# 130812_AriloTX_FINAL.net
KiCad netlist of a schematic drawn in EAGLE
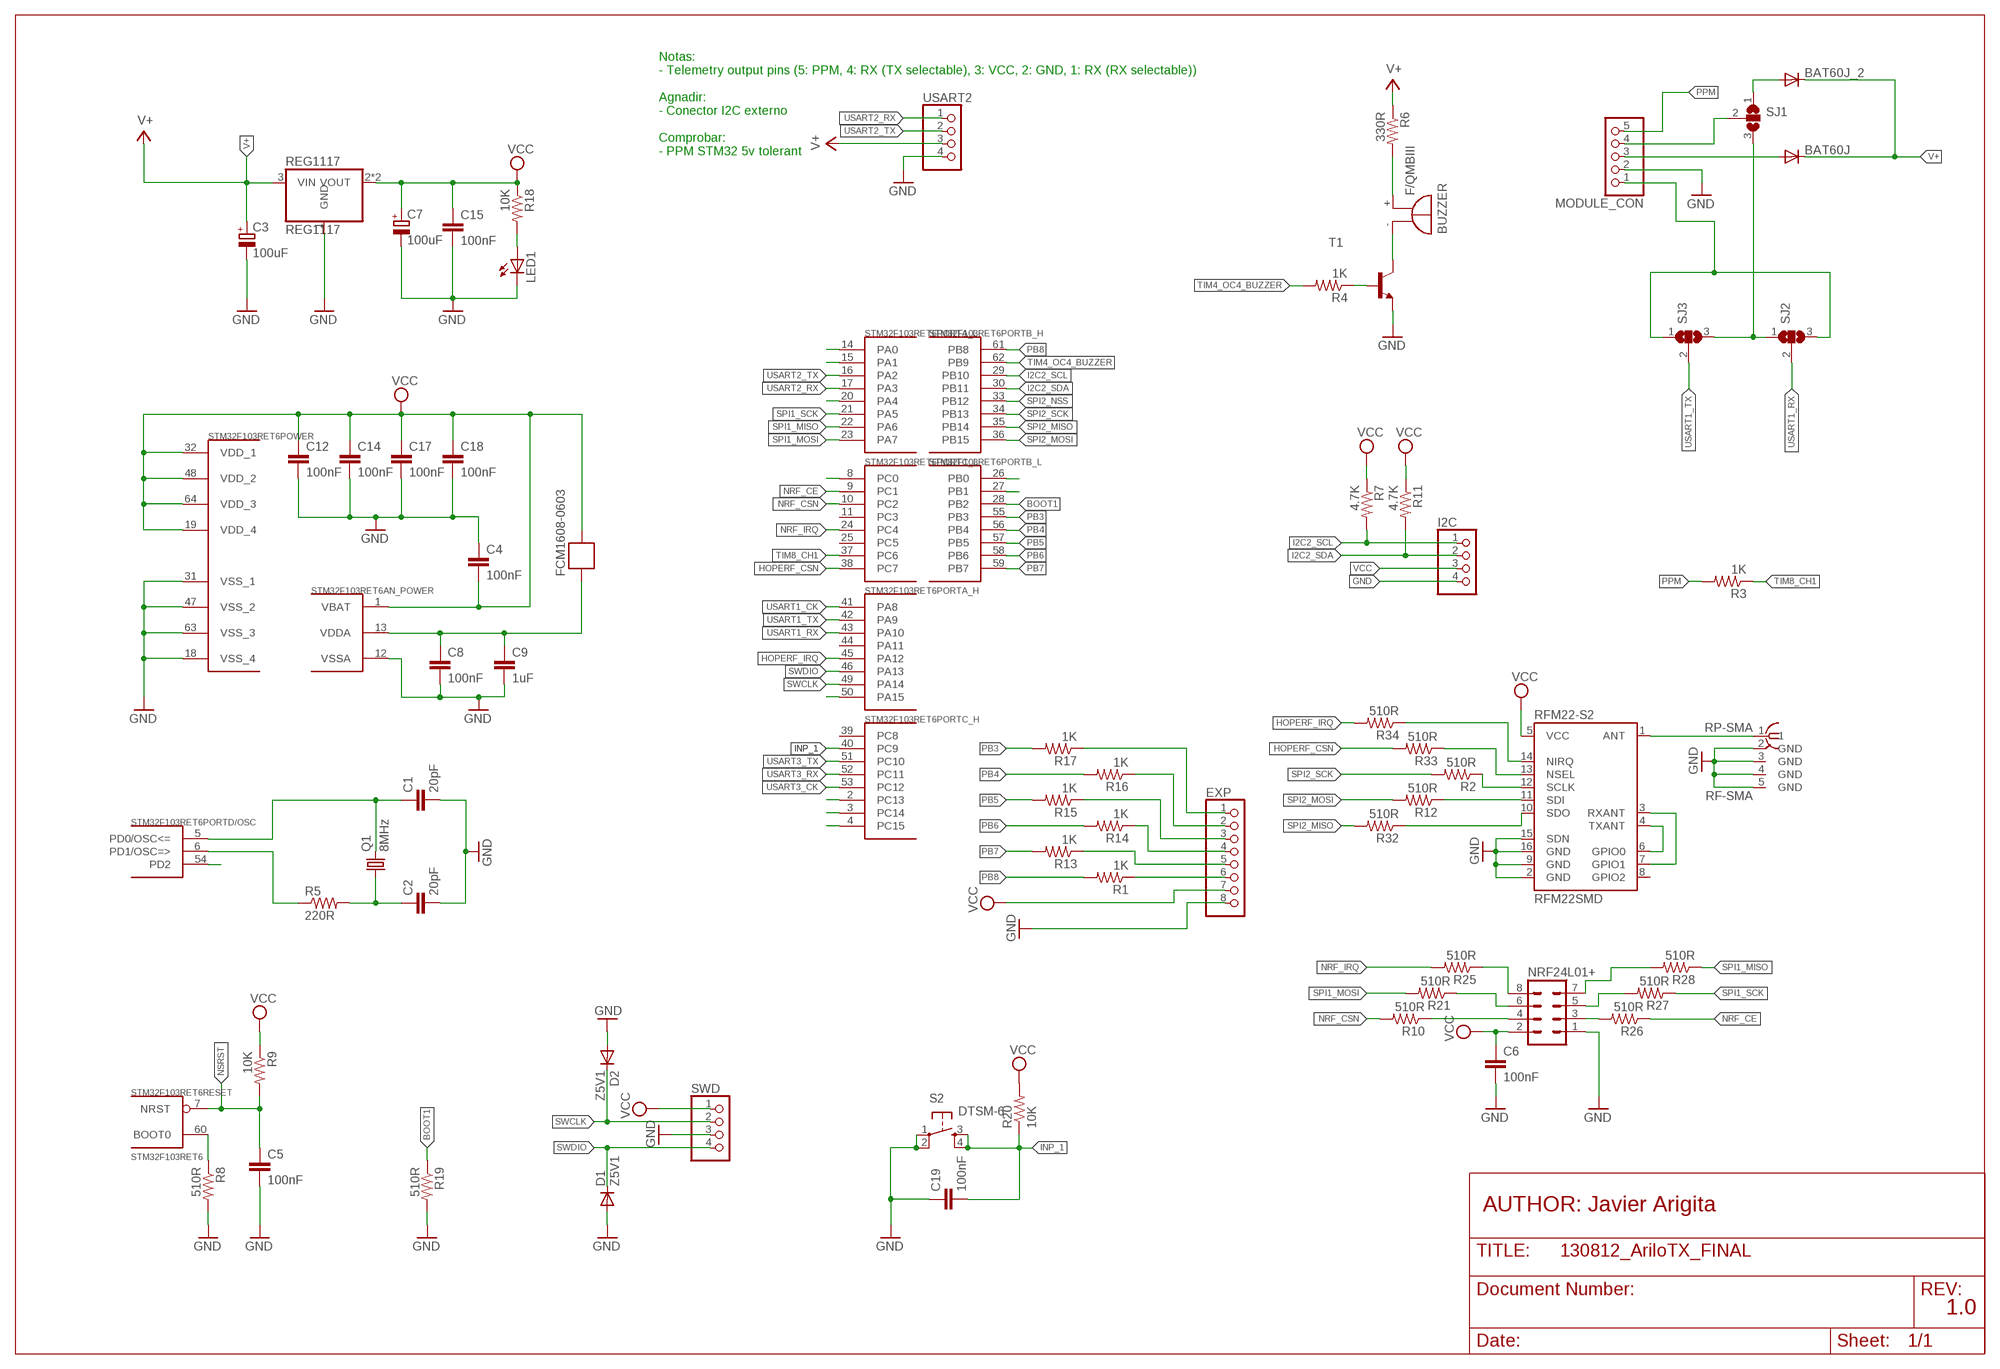
[diagram p0: schematic, sheet 1]

(export (version "E")
  (design (tool "Eeschema 10.0.6"))
  (components
    (comp (ref "BAT60J")
      (value "DIODE-SOD323-R")
      (footprint "eagle-import:SOD323-R")
      (libsource (lib "eagle-import") (part "DIODE-SOD323-R"))
    )
    (comp (ref "BAT60J_2")
      (value "DIODE-SOD323-R")
      (footprint "eagle-import:SOD323-R")
      (libsource (lib "eagle-import") (part "DIODE-SOD323-R"))
    )
    (comp (ref "BUZZER")
      (value "F/QMBIII")
      (footprint "eagle-import:F_QMBIII")
      (libsource (lib "eagle-import") (part "F/QMBIII"))
    )
    (comp (ref "C1")
      (value "20pF")
      (footprint "eagle-import:C0805")
      (libsource (lib "eagle-import") (part "C-EUC0805"))
    )
    (comp (ref "C2")
      (value "20pF")
      (footprint "eagle-import:C0805")
      (libsource (lib "eagle-import") (part "C-EUC0805"))
    )
    (comp (ref "C3")
      (value "100uF")
      (footprint "eagle-import:SMC_B")
      (libsource (lib "eagle-import") (part "CPOL-EUSMCB"))
    )
    (comp (ref "C4")
      (value "100nF")
      (footprint "eagle-import:C0805")
      (libsource (lib "eagle-import") (part "C-EUC0805"))
    )
    (comp (ref "C5")
      (value "100nF")
      (footprint "eagle-import:C0805")
      (libsource (lib "eagle-import") (part "C-EUC0805"))
    )
    (comp (ref "C6")
      (value "100nF")
      (footprint "eagle-import:C0805")
      (libsource (lib "eagle-import") (part "C-EUC0805"))
    )
    (comp (ref "C7")
      (value "100uF")
      (footprint "eagle-import:SMC_B")
      (libsource (lib "eagle-import") (part "CPOL-EUSMCB"))
    )
    (comp (ref "C8")
      (value "100nF")
      (footprint "eagle-import:C0805")
      (libsource (lib "eagle-import") (part "C-EUC0805"))
    )
    (comp (ref "C9")
      (value "1uF")
      (footprint "eagle-import:C3216")
      (libsource (lib "eagle-import") (part "resistor_C-EUC3216"))
    )
    (comp (ref "C12")
      (value "100nF")
      (footprint "eagle-import:C0805")
      (libsource (lib "eagle-import") (part "C-EUC0805"))
    )
    (comp (ref "C14")
      (value "100nF")
      (footprint "eagle-import:C0805")
      (libsource (lib "eagle-import") (part "C-EUC0805"))
    )
    (comp (ref "C15")
      (value "100nF")
      (footprint "eagle-import:C0805")
      (libsource (lib "eagle-import") (part "C-EUC0805"))
    )
    (comp (ref "C17")
      (value "100nF")
      (footprint "eagle-import:C0805")
      (libsource (lib "eagle-import") (part "C-EUC0805"))
    )
    (comp (ref "C18")
      (value "100nF")
      (footprint "eagle-import:C0805")
      (libsource (lib "eagle-import") (part "C-EUC0805"))
    )
    (comp (ref "C19")
      (value "100nF")
      (footprint "eagle-import:C0805")
      (libsource (lib "eagle-import") (part "C-EUC0805"))
    )
    (comp (ref "D1")
      (value "Z5V1")
      (footprint "eagle-import:SOD323-R")
      (libsource (lib "eagle-import") (part "DIODE-SOD323-R"))
    )
    (comp (ref "D2")
      (value "Z5V1")
      (footprint "eagle-import:SOD323-R")
      (libsource (lib "eagle-import") (part "DIODE-SOD323-R"))
    )
    (comp (ref "EXP")
      (value "PINHD-1X8")
      (footprint "eagle-import:1X08")
      (libsource (lib "eagle-import") (part "PINHD-1X8"))
    )
    (comp (ref "FCM1608-0603")
      (value "FERRITE-BEAD")
      (footprint "eagle-import:R0603")
      (libsource (lib "eagle-import") (part "FERRITE-BEAD"))
    )
    (comp (ref "I2C")
      (value "PINHD-1X4")
      (footprint "eagle-import:1X04")
      (libsource (lib "eagle-import") (part "PINHD-1X4"))
    )
    (comp (ref "LED1")
      (value "LED0805")
      (footprint "eagle-import:CHIPLED_0805")
      (libsource (lib "eagle-import") (part "LED0805"))
    )
    (comp (ref "MODULE_CON")
      (value "PINHD-1X5")
      (footprint "eagle-import:1X05")
      (libsource (lib "eagle-import") (part "PINHD-1X5"))
    )
    (comp (ref "NRF24L01+")
      (value "MA04-2")
      (footprint "eagle-import:MA04-2")
      (libsource (lib "eagle-import") (part "MA04-2"))
    )
    (comp (ref "Q1")
      (value "8MHz")
      (footprint "eagle-import:SM49")
      (libsource (lib "eagle-import") (part "CRYSTALSM49"))
    )
    (comp (ref "R1")
      (value "1K")
      (footprint "eagle-import:R0805")
      (libsource (lib "eagle-import") (part "RESISTOR0805"))
    )
    (comp (ref "R2")
      (value "510R")
      (footprint "eagle-import:R0805")
      (libsource (lib "eagle-import") (part "RESISTOR0805"))
    )
    (comp (ref "R3")
      (value "1K")
      (footprint "eagle-import:R0805")
      (libsource (lib "eagle-import") (part "RESISTOR0805"))
    )
    (comp (ref "R4")
      (value "1K")
      (footprint "eagle-import:R0805")
      (libsource (lib "eagle-import") (part "RESISTOR0805"))
    )
    (comp (ref "R5")
      (value "220R")
      (footprint "eagle-import:R0805")
      (libsource (lib "eagle-import") (part "RESISTOR0805"))
    )
    (comp (ref "R6")
      (value "330R")
      (footprint "eagle-import:R0805")
      (libsource (lib "eagle-import") (part "RESISTOR0805"))
    )
    (comp (ref "R7")
      (value "4.7K")
      (footprint "eagle-import:R0805")
      (libsource (lib "eagle-import") (part "RESISTOR0805"))
    )
    (comp (ref "R8")
      (value "510R")
      (footprint "eagle-import:R0805")
      (libsource (lib "eagle-import") (part "RESISTOR0805"))
    )
    (comp (ref "R9")
      (value "10K")
      (footprint "eagle-import:R0805")
      (libsource (lib "eagle-import") (part "RESISTOR0805"))
    )
    (comp (ref "R10")
      (value "510R")
      (footprint "eagle-import:R0805")
      (libsource (lib "eagle-import") (part "RESISTOR0805"))
    )
    (comp (ref "R11")
      (value "4.7K")
      (footprint "eagle-import:R0805")
      (libsource (lib "eagle-import") (part "RESISTOR0805"))
    )
    (comp (ref "R12")
      (value "510R")
      (footprint "eagle-import:R0805")
      (libsource (lib "eagle-import") (part "RESISTOR0805"))
    )
    (comp (ref "R13")
      (value "1K")
      (footprint "eagle-import:R0805")
      (libsource (lib "eagle-import") (part "RESISTOR0805"))
    )
    (comp (ref "R14")
      (value "1K")
      (footprint "eagle-import:R0805")
      (libsource (lib "eagle-import") (part "RESISTOR0805"))
    )
    (comp (ref "R15")
      (value "1K")
      (footprint "eagle-import:R0805")
      (libsource (lib "eagle-import") (part "RESISTOR0805"))
    )
    (comp (ref "R16")
      (value "1K")
      (footprint "eagle-import:R0805")
      (libsource (lib "eagle-import") (part "RESISTOR0805"))
    )
    (comp (ref "R17")
      (value "1K")
      (footprint "eagle-import:R0805")
      (libsource (lib "eagle-import") (part "RESISTOR0805"))
    )
    (comp (ref "R18")
      (value "10K")
      (footprint "eagle-import:R0805")
      (libsource (lib "eagle-import") (part "RESISTOR0805"))
    )
    (comp (ref "R19")
      (value "510R")
      (footprint "eagle-import:R0805")
      (libsource (lib "eagle-import") (part "RESISTOR0805"))
    )
    (comp (ref "R20")
      (value "10K")
      (footprint "eagle-import:R0805")
      (libsource (lib "eagle-import") (part "RESISTOR0805"))
    )
    (comp (ref "R21")
      (value "510R")
      (footprint "eagle-import:R0805")
      (libsource (lib "eagle-import") (part "RESISTOR0805"))
    )
    (comp (ref "R25")
      (value "510R")
      (footprint "eagle-import:R0805")
      (libsource (lib "eagle-import") (part "RESISTOR0805"))
    )
    (comp (ref "R26")
      (value "510R")
      (footprint "eagle-import:R0805")
      (libsource (lib "eagle-import") (part "RESISTOR0805"))
    )
    (comp (ref "R27")
      (value "510R")
      (footprint "eagle-import:R0805")
      (libsource (lib "eagle-import") (part "RESISTOR0805"))
    )
    (comp (ref "R28")
      (value "510R")
      (footprint "eagle-import:R0805")
      (libsource (lib "eagle-import") (part "RESISTOR0805"))
    )
    (comp (ref "R32")
      (value "510R")
      (footprint "eagle-import:R0805")
      (libsource (lib "eagle-import") (part "RESISTOR0805"))
    )
    (comp (ref "R33")
      (value "510R")
      (footprint "eagle-import:R0805")
      (libsource (lib "eagle-import") (part "RESISTOR0805"))
    )
    (comp (ref "R34")
      (value "510R")
      (footprint "eagle-import:R0805")
      (libsource (lib "eagle-import") (part "RESISTOR0805"))
    )
    (comp (ref "REG1117")
      (value "REG1117")
      (footprint "eagle-import:SOT223")
      (libsource (lib "eagle-import") (part "REG1117"))
    )
    (comp (ref "RFM22-S2")
      (value "RFM22SMD")
      (footprint "eagle-import:RFM22-XXX-S2")
      (libsource (lib "eagle-import") (part "RFM22SMD"))
    )
    (comp (ref "RP-SMA")
      (value "RF-SMA")
      (footprint "eagle-import:BU-SMA-H")
      (libsource (lib "eagle-import") (part "RF-SMA"))
    )
    (comp (ref "S2")
      (value "DTSM-6")
      (footprint "eagle-import:DTSM-6")
      (libsource (lib "eagle-import") (part "DTSM-6"))
    )
    (comp (ref "SJ1")
      (value "SJ2W")
      (footprint "eagle-import:SJ_2")
      (libsource (lib "eagle-import") (part "SJ2W"))
    )
    (comp (ref "SJ2")
      (value "SJ2W")
      (footprint "eagle-import:SJ_2")
      (libsource (lib "eagle-import") (part "SJ2W"))
    )
    (comp (ref "SJ3")
      (value "SJ2W")
      (footprint "eagle-import:SJ_2")
      (libsource (lib "eagle-import") (part "SJ2W"))
    )
    (comp (ref "STM32F103RET6")
      (value "STM32F103RET6")
      (footprint "eagle-import:TQFP64")
      (libsource (lib "eagle-import") (part "STM32F10XRXT6"))
    )
    (comp (ref "SWD")
      (value "PINHD-1X4")
      (footprint "eagle-import:1X04")
      (libsource (lib "eagle-import") (part "PINHD-1X4"))
    )
    (comp (ref "T1")
      (value "BC848-NPN-SOT23-BEC")
      (footprint "eagle-import:SOT23-BEC")
      (libsource (lib "eagle-import") (part "-NPN-SOT23-BECBC848"))
    )
    (comp (ref "USART2")
      (value "PINHD-1X4")
      (footprint "eagle-import:1X04")
      (libsource (lib "eagle-import") (part "PINHD-1X4"))
    )
  )
  (nets
    (net (code "1") (name "BOOT1") (class "Default")
      (node (ref "R19") (pin "1") (pinfunction "1_1") (pintype "passive"))
      (node (ref "STM32F103RET6") (pin "28") (pinfunction "PB2_28") (pintype "bidirectional"))
    )
    (net (code "2") (name "GND") (class "Default")
      (node (ref "C1") (pin "2") (pinfunction "2_2") (pintype "passive"))
      (node (ref "C12") (pin "2") (pinfunction "2_2") (pintype "passive"))
      (node (ref "C14") (pin "2") (pinfunction "2_2") (pintype "passive"))
      (node (ref "C15") (pin "2") (pinfunction "2_2") (pintype "passive"))
      (node (ref "C17") (pin "2") (pinfunction "2_2") (pintype "passive"))
      (node (ref "C18") (pin "2") (pinfunction "2_2") (pintype "passive"))
      (node (ref "C19") (pin "1") (pinfunction "1_1") (pintype "passive"))
      (node (ref "C2") (pin "2") (pinfunction "2_2") (pintype "passive"))
      (node (ref "C3") (pin "-") (pinfunction "-_-") (pintype "passive"))
      (node (ref "C4") (pin "1") (pinfunction "1_1") (pintype "passive"))
      (node (ref "C5") (pin "2") (pinfunction "2_2") (pintype "passive"))
      (node (ref "C6") (pin "2") (pinfunction "2_2") (pintype "passive"))
      (node (ref "C7") (pin "-") (pinfunction "-_-") (pintype "passive"))
      (node (ref "C8") (pin "2") (pinfunction "2_2") (pintype "passive"))
      (node (ref "C9") (pin "2") (pinfunction "2_2") (pintype "passive"))
      (node (ref "D1") (pin "A") (pinfunction "A_A") (pintype "passive"))
      (node (ref "D2") (pin "A") (pinfunction "A_A") (pintype "passive"))
      (node (ref "EXP") (pin "8") (pinfunction "8_8") (pintype "passive"))
      (node (ref "I2C") (pin "4") (pinfunction "4_4") (pintype "passive"))
      (node (ref "LED1") (pin "C") (pinfunction "C_C") (pintype "passive"))
      (node (ref "MODULE_CON") (pin "2") (pinfunction "2_2") (pintype "passive"))
      (node (ref "NRF24L01+") (pin "1") (pinfunction "1_1") (pintype "passive"))
      (node (ref "R19") (pin "2") (pinfunction "2_2") (pintype "passive"))
      (node (ref "R8") (pin "2") (pinfunction "2_2") (pintype "passive"))
      (node (ref "REG1117") (pin "1") (pinfunction "GND_1") (pintype "power_in"))
      (node (ref "RFM22-S2") (pin "15") (pinfunction "SDN_15") (pintype "input"))
      (node (ref "RFM22-S2") (pin "16") (pinfunction "GND_16") (pintype "power_in"))
      (node (ref "RFM22-S2") (pin "2") (pinfunction "GND_2") (pintype "power_in"))
      (node (ref "RFM22-S2") (pin "9") (pinfunction "GND_9") (pintype "power_in"))
      (node (ref "RP-SMA") (pin "2") (pinfunction "GND_2") (pintype "power_in"))
      (node (ref "RP-SMA") (pin "3") (pinfunction "GND_3") (pintype "bidirectional"))
      (node (ref "RP-SMA") (pin "4") (pinfunction "GND_4") (pintype "bidirectional"))
      (node (ref "RP-SMA") (pin "5") (pinfunction "GND_5") (pintype "bidirectional"))
      (node (ref "S2") (pin "1") (pinfunction "1_1") (pintype "passive"))
      (node (ref "S2") (pin "2") (pinfunction "2_2") (pintype "passive"))
      (node (ref "STM32F103RET6") (pin "12") (pinfunction "VSSA_12") (pintype "power_in"))
      (node (ref "STM32F103RET6") (pin "18") (pinfunction "VSS_4_18") (pintype "power_in"))
      (node (ref "STM32F103RET6") (pin "31") (pinfunction "VSS_1_31") (pintype "power_in"))
      (node (ref "STM32F103RET6") (pin "47") (pinfunction "VSS_2_47") (pintype "power_in"))
      (node (ref "STM32F103RET6") (pin "63") (pinfunction "VSS_3_63") (pintype "power_in"))
      (node (ref "SWD") (pin "3") (pinfunction "3_3") (pintype "passive"))
      (node (ref "T1") (pin "E") (pinfunction "E_E") (pintype "passive"))
      (node (ref "USART2") (pin "4") (pinfunction "4_4") (pintype "passive"))
    )
    (net (code "3") (name "HOPERF_CSN") (class "Default")
      (node (ref "R33") (pin "2") (pinfunction "2_2") (pintype "passive"))
      (node (ref "STM32F103RET6") (pin "38") (pinfunction "PC7_38") (pintype "bidirectional"))
    )
    (net (code "4") (name "HOPERF_IRQ") (class "Default")
      (node (ref "R34") (pin "2") (pinfunction "2_2") (pintype "passive"))
      (node (ref "STM32F103RET6") (pin "45") (pinfunction "PA12_45") (pintype "bidirectional"))
    )
    (net (code "5") (name "I2C2_SCL") (class "Default")
      (node (ref "I2C") (pin "1") (pinfunction "1_1") (pintype "passive"))
      (node (ref "R7") (pin "2") (pinfunction "2_2") (pintype "passive"))
      (node (ref "STM32F103RET6") (pin "29") (pinfunction "PB10_29") (pintype "bidirectional"))
    )
    (net (code "6") (name "I2C2_SDA") (class "Default")
      (node (ref "I2C") (pin "2") (pinfunction "2_2") (pintype "passive"))
      (node (ref "R11") (pin "2") (pinfunction "2_2") (pintype "passive"))
      (node (ref "STM32F103RET6") (pin "30") (pinfunction "PB11_30") (pintype "bidirectional"))
    )
    (net (code "7") (name "INP_1") (class "Default")
      (node (ref "C19") (pin "2") (pinfunction "2_2") (pintype "passive"))
      (node (ref "R20") (pin "1") (pinfunction "1_1") (pintype "passive"))
      (node (ref "S2") (pin "3") (pinfunction "3_3") (pintype "passive"))
      (node (ref "S2") (pin "4") (pinfunction "4_4") (pintype "passive"))
      (node (ref "STM32F103RET6") (pin "40") (pinfunction "PC9_40") (pintype "bidirectional"))
    )
    (net (code "8") (name "NRF_CE") (class "Default")
      (node (ref "R26") (pin "1") (pinfunction "1_1") (pintype "passive"))
      (node (ref "STM32F103RET6") (pin "9") (pinfunction "PC1_9") (pintype "bidirectional"))
    )
    (net (code "9") (name "NRF_CSN") (class "Default")
      (node (ref "R10") (pin "2") (pinfunction "2_2") (pintype "passive"))
      (node (ref "STM32F103RET6") (pin "10") (pinfunction "PC2_10") (pintype "bidirectional"))
    )
    (net (code "10") (name "NRF_IRQ") (class "Default")
      (node (ref "R25") (pin "2") (pinfunction "2_2") (pintype "passive"))
      (node (ref "STM32F103RET6") (pin "24") (pinfunction "PC4_24") (pintype "bidirectional"))
    )
    (net (code "11") (name "NSRST") (class "Default")
      (node (ref "C5") (pin "1") (pinfunction "1_1") (pintype "passive"))
      (node (ref "R9") (pin "2") (pinfunction "2_2") (pintype "passive"))
      (node (ref "STM32F103RET6") (pin "7") (pinfunction "NRST_7") (pintype "input"))
    )
    (net (code "12") (name "Net-(BAT60J-PadA)") (class "Default")
      (node (ref "BAT60J") (pin "A") (pinfunction "A_A") (pintype "passive"))
      (node (ref "MODULE_CON") (pin "3") (pinfunction "3_3") (pintype "passive"))
    )
    (net (code "13") (name "Net-(BAT60J_2-PadA)") (class "Default")
      (node (ref "BAT60J_2") (pin "A") (pinfunction "A_A") (pintype "passive"))
      (node (ref "SJ1") (pin "1") (pinfunction "1_1") (pintype "passive"))
    )
    (net (code "14") (name "Net-(BUZZER-+)") (class "Default")
      (node (ref "BUZZER") (pin "-") (pinfunction "+_-") (pintype "passive"))
      (node (ref "T1") (pin "C") (pinfunction "C_C") (pintype "passive"))
    )
    (net (code "15") (name "Net-(BUZZER--)") (class "Default")
      (node (ref "BUZZER") (pin "+") (pinfunction "-_+") (pintype "passive"))
      (node (ref "R6") (pin "2") (pinfunction "2_2") (pintype "passive"))
    )
    (net (code "16") (name "Net-(C2-Pad1)") (class "Default")
      (node (ref "C2") (pin "1") (pinfunction "1_1") (pintype "passive"))
      (node (ref "Q1") (pin "1") (pinfunction "1_1") (pintype "passive"))
      (node (ref "R5") (pin "2") (pinfunction "2_2") (pintype "passive"))
    )
    (net (code "17") (name "Net-(EXP-Pad1)") (class "Default")
      (node (ref "EXP") (pin "1") (pinfunction "1_1") (pintype "passive"))
      (node (ref "R17") (pin "1") (pinfunction "1_1") (pintype "passive"))
    )
    (net (code "18") (name "Net-(EXP-Pad2)") (class "Default")
      (node (ref "EXP") (pin "2") (pinfunction "2_2") (pintype "passive"))
      (node (ref "R16") (pin "1") (pinfunction "1_1") (pintype "passive"))
    )
    (net (code "19") (name "Net-(EXP-Pad3)") (class "Default")
      (node (ref "EXP") (pin "3") (pinfunction "3_3") (pintype "passive"))
      (node (ref "R15") (pin "1") (pinfunction "1_1") (pintype "passive"))
    )
    (net (code "20") (name "Net-(EXP-Pad4)") (class "Default")
      (node (ref "EXP") (pin "4") (pinfunction "4_4") (pintype "passive"))
      (node (ref "R14") (pin "1") (pinfunction "1_1") (pintype "passive"))
    )
    (net (code "21") (name "Net-(EXP-Pad5)") (class "Default")
      (node (ref "EXP") (pin "5") (pinfunction "5_5") (pintype "passive"))
      (node (ref "R13") (pin "1") (pinfunction "1_1") (pintype "passive"))
    )
    (net (code "22") (name "Net-(EXP-Pad6)") (class "Default")
      (node (ref "EXP") (pin "6") (pinfunction "6_6") (pintype "passive"))
      (node (ref "R1") (pin "1") (pinfunction "1_1") (pintype "passive"))
    )
    (net (code "23") (name "Net-(FCM1608-0603-P$2)") (class "Default")
      (node (ref "C8") (pin "1") (pinfunction "1_1") (pintype "passive"))
      (node (ref "C9") (pin "1") (pinfunction "1_1") (pintype "passive"))
      (node (ref "FCM1608-0603") (pin "2") (pinfunction "P$2_2") (pintype "bidirectional"))
      (node (ref "STM32F103RET6") (pin "13") (pinfunction "VDDA_13") (pintype "power_in"))
    )
    (net (code "24") (name "Net-(LED1-PadA)") (class "Default")
      (node (ref "LED1") (pin "A") (pinfunction "A_A") (pintype "passive"))
      (node (ref "R18") (pin "2") (pinfunction "2_2") (pintype "passive"))
    )
    (net (code "25") (name "Net-(MODULE_CON-Pad1)") (class "Default")
      (node (ref "MODULE_CON") (pin "1") (pinfunction "1_1") (pintype "passive"))
      (node (ref "SJ2") (pin "3") (pinfunction "3_3") (pintype "passive"))
      (node (ref "SJ3") (pin "1") (pinfunction "1_1") (pintype "passive"))
    )
    (net (code "26") (name "Net-(MODULE_CON-Pad4)") (class "Default")
      (node (ref "MODULE_CON") (pin "4") (pinfunction "4_4") (pintype "passive"))
      (node (ref "SJ1") (pin "2") (pinfunction "2_2") (pintype "passive"))
    )
    (net (code "27") (name "Net-(NRF24L01+-Pad3)") (class "Default")
      (node (ref "NRF24L01+") (pin "3") (pinfunction "3_3") (pintype "passive"))
      (node (ref "R26") (pin "2") (pinfunction "2_2") (pintype "passive"))
    )
    (net (code "28") (name "Net-(NRF24L01+-Pad4)") (class "Default")
      (node (ref "NRF24L01+") (pin "4") (pinfunction "4_4") (pintype "passive"))
      (node (ref "R10") (pin "1") (pinfunction "1_1") (pintype "passive"))
    )
    (net (code "29") (name "Net-(NRF24L01+-Pad5)") (class "Default")
      (node (ref "NRF24L01+") (pin "5") (pinfunction "5_5") (pintype "passive"))
      (node (ref "R27") (pin "2") (pinfunction "2_2") (pintype "passive"))
    )
    (net (code "30") (name "Net-(NRF24L01+-Pad6)") (class "Default")
      (node (ref "NRF24L01+") (pin "6") (pinfunction "6_6") (pintype "passive"))
      (node (ref "R21") (pin "1") (pinfunction "1_1") (pintype "passive"))
    )
    (net (code "31") (name "Net-(NRF24L01+-Pad7)") (class "Default")
      (node (ref "NRF24L01+") (pin "7") (pinfunction "7_7") (pintype "passive"))
      (node (ref "R28") (pin "2") (pinfunction "2_2") (pintype "passive"))
    )
    (net (code "32") (name "Net-(NRF24L01+-Pad8)") (class "Default")
      (node (ref "NRF24L01+") (pin "8") (pinfunction "8_8") (pintype "passive"))
      (node (ref "R25") (pin "1") (pinfunction "1_1") (pintype "passive"))
    )
    (net (code "33") (name "Net-(R4-Pad1)") (class "Default")
      (node (ref "R4") (pin "1") (pinfunction "1_1") (pintype "passive"))
      (node (ref "T1") (pin "B") (pinfunction "B_B") (pintype "passive"))
    )
    (net (code "34") (name "Net-(RFM22-S2-ANT)") (class "Default")
      (node (ref "RFM22-S2") (pin "1") (pinfunction "ANT_1") (pintype "bidirectional"))
      (node (ref "RP-SMA") (pin "1") (pinfunction "1_1") (pintype "passive"))
    )
    (net (code "35") (name "Net-(RFM22-S2-GPIO0)") (class "Default")
      (node (ref "RFM22-S2") (pin "4") (pinfunction "TXANT_4") (pintype "input"))
      (node (ref "RFM22-S2") (pin "6") (pinfunction "GPIO0_6") (pintype "bidirectional"))
    )
    (net (code "36") (name "Net-(RFM22-S2-GPIO1)") (class "Default")
      (node (ref "RFM22-S2") (pin "3") (pinfunction "RXANT_3") (pintype "input"))
      (node (ref "RFM22-S2") (pin "7") (pinfunction "GPIO1_7") (pintype "bidirectional"))
    )
    (net (code "37") (name "Net-(RFM22-S2-NIRQ)") (class "Default")
      (node (ref "R34") (pin "1") (pinfunction "1_1") (pintype "passive"))
      (node (ref "RFM22-S2") (pin "14") (pinfunction "NIRQ_14") (pintype "output"))
    )
    (net (code "38") (name "Net-(RFM22-S2-NSEL)") (class "Default")
      (node (ref "R33") (pin "1") (pinfunction "1_1") (pintype "passive"))
      (node (ref "RFM22-S2") (pin "13") (pinfunction "NSEL_13") (pintype "input"))
    )
    (net (code "39") (name "Net-(RFM22-S2-SCLK)") (class "Default")
      (node (ref "R2") (pin "1") (pinfunction "1_1") (pintype "passive"))
      (node (ref "RFM22-S2") (pin "12") (pinfunction "SCLK_12") (pintype "input"))
    )
    (net (code "40") (name "Net-(RFM22-S2-SDI)") (class "Default")
      (node (ref "R12") (pin "1") (pinfunction "1_1") (pintype "passive"))
      (node (ref "RFM22-S2") (pin "11") (pinfunction "SDI_11") (pintype "input"))
    )
    (net (code "41") (name "Net-(RFM22-S2-SDO)") (class "Default")
      (node (ref "R32") (pin "1") (pinfunction "1_1") (pintype "passive"))
      (node (ref "RFM22-S2") (pin "10") (pinfunction "SDO_10") (pintype "output"))
    )
    (net (code "42") (name "Net-(SJ1-Pad3)") (class "Default")
      (node (ref "SJ1") (pin "3") (pinfunction "3_3") (pintype "passive"))
      (node (ref "SJ2") (pin "1") (pinfunction "1_1") (pintype "passive"))
      (node (ref "SJ3") (pin "3") (pinfunction "3_3") (pintype "passive"))
    )
    (net (code "43") (name "Net-(STM32F103RET6H-PD0{slash}OSC<=)") (class "Default")
      (node (ref "C1") (pin "1") (pinfunction "1_1") (pintype "passive"))
      (node (ref "Q1") (pin "2") (pinfunction "2_2") (pintype "passive"))
      (node (ref "STM32F103RET6") (pin "5") (pinfunction "PD0/OSC<=_5") (pintype "bidirectional"))
    )
    (net (code "44") (name "Net-(STM32F103RET6H-PD1{slash}OSC=>)") (class "Default")
      (node (ref "R5") (pin "1") (pinfunction "1_1") (pintype "passive"))
      (node (ref "STM32F103RET6") (pin "6") (pinfunction "PD1/OSC=>_6") (pintype "bidirectional"))
    )
    (net (code "45") (name "Net-(STM32F103RET6J-BOOT0)") (class "Default")
      (node (ref "R8") (pin "1") (pinfunction "1_1") (pintype "passive"))
      (node (ref "STM32F103RET6") (pin "60") (pinfunction "BOOT0_60") (pintype "input"))
    )
    (net (code "46") (name "PB3") (class "Default")
      (node (ref "R17") (pin "2") (pinfunction "2_2") (pintype "passive"))
      (node (ref "STM32F103RET6") (pin "55") (pinfunction "PB3_55") (pintype "bidirectional"))
    )
    (net (code "47") (name "PB4") (class "Default")
      (node (ref "R16") (pin "2") (pinfunction "2_2") (pintype "passive"))
      (node (ref "STM32F103RET6") (pin "56") (pinfunction "PB4_56") (pintype "bidirectional"))
    )
    (net (code "48") (name "PB5") (class "Default")
      (node (ref "R15") (pin "2") (pinfunction "2_2") (pintype "passive"))
      (node (ref "STM32F103RET6") (pin "57") (pinfunction "PB5_57") (pintype "bidirectional"))
    )
    (net (code "49") (name "PB6") (class "Default")
      (node (ref "R14") (pin "2") (pinfunction "2_2") (pintype "passive"))
      (node (ref "STM32F103RET6") (pin "58") (pinfunction "PB6_58") (pintype "bidirectional"))
    )
    (net (code "50") (name "PB7") (class "Default")
      (node (ref "R13") (pin "2") (pinfunction "2_2") (pintype "passive"))
      (node (ref "STM32F103RET6") (pin "59") (pinfunction "PB7_59") (pintype "bidirectional"))
    )
    (net (code "51") (name "PB8") (class "Default")
      (node (ref "R1") (pin "2") (pinfunction "2_2") (pintype "passive"))
      (node (ref "STM32F103RET6") (pin "61") (pinfunction "PB8_61") (pintype "bidirectional"))
    )
    (net (code "52") (name "PPM") (class "Default")
      (node (ref "MODULE_CON") (pin "5") (pinfunction "5_5") (pintype "passive"))
      (node (ref "R3") (pin "2") (pinfunction "2_2") (pintype "passive"))
    )
    (net (code "53") (name "SPI1_MISO") (class "Default")
      (node (ref "R28") (pin "1") (pinfunction "1_1") (pintype "passive"))
      (node (ref "STM32F103RET6") (pin "22") (pinfunction "PA6_22") (pintype "bidirectional"))
    )
    (net (code "54") (name "SPI1_MOSI") (class "Default")
      (node (ref "R21") (pin "2") (pinfunction "2_2") (pintype "passive"))
      (node (ref "STM32F103RET6") (pin "23") (pinfunction "PA7_23") (pintype "bidirectional"))
    )
    (net (code "55") (name "SPI1_SCK") (class "Default")
      (node (ref "R27") (pin "1") (pinfunction "1_1") (pintype "passive"))
      (node (ref "STM32F103RET6") (pin "21") (pinfunction "PA5_21") (pintype "bidirectional"))
    )
    (net (code "56") (name "SPI2_MISO") (class "Default")
      (node (ref "R32") (pin "2") (pinfunction "2_2") (pintype "passive"))
      (node (ref "STM32F103RET6") (pin "35") (pinfunction "PB14_35") (pintype "bidirectional"))
    )
    (net (code "57") (name "SPI2_MOSI") (class "Default")
      (node (ref "R12") (pin "2") (pinfunction "2_2") (pintype "passive"))
      (node (ref "STM32F103RET6") (pin "36") (pinfunction "PB15_36") (pintype "bidirectional"))
    )
    (net (code "58") (name "SPI2_NSS") (class "Default")
      (node (ref "STM32F103RET6") (pin "33") (pinfunction "PB12_33") (pintype "bidirectional"))
    )
    (net (code "59") (name "SPI2_SCK") (class "Default")
      (node (ref "R2") (pin "2") (pinfunction "2_2") (pintype "passive"))
      (node (ref "STM32F103RET6") (pin "34") (pinfunction "PB13_34") (pintype "bidirectional"))
    )
    (net (code "60") (name "SWCLK") (class "Default")
      (node (ref "D2") (pin "C") (pinfunction "C_C") (pintype "passive"))
      (node (ref "STM32F103RET6") (pin "49") (pinfunction "PA14_49") (pintype "bidirectional"))
      (node (ref "SWD") (pin "2") (pinfunction "2_2") (pintype "passive"))
    )
    (net (code "61") (name "SWDIO") (class "Default")
      (node (ref "D1") (pin "C") (pinfunction "C_C") (pintype "passive"))
      (node (ref "STM32F103RET6") (pin "46") (pinfunction "PA13_46") (pintype "bidirectional"))
      (node (ref "SWD") (pin "4") (pinfunction "4_4") (pintype "passive"))
    )
    (net (code "62") (name "TIM4_OC4_BUZZER") (class "Default")
      (node (ref "R4") (pin "2") (pinfunction "2_2") (pintype "passive"))
      (node (ref "STM32F103RET6") (pin "62") (pinfunction "PB9_62") (pintype "bidirectional"))
    )
    (net (code "63") (name "TIM8_CH1") (class "Default")
      (node (ref "R3") (pin "1") (pinfunction "1_1") (pintype "passive"))
      (node (ref "STM32F103RET6") (pin "37") (pinfunction "PC6_37") (pintype "bidirectional"))
    )
    (net (code "64") (name "USART1_CK") (class "Default")
      (node (ref "STM32F103RET6") (pin "41") (pinfunction "PA8_41") (pintype "bidirectional"))
    )
    (net (code "65") (name "USART1_RX") (class "Default")
      (node (ref "SJ2") (pin "2") (pinfunction "2_2") (pintype "passive"))
      (node (ref "STM32F103RET6") (pin "43") (pinfunction "PA10_43") (pintype "bidirectional"))
    )
    (net (code "66") (name "USART1_TX") (class "Default")
      (node (ref "SJ3") (pin "2") (pinfunction "2_2") (pintype "passive"))
      (node (ref "STM32F103RET6") (pin "42") (pinfunction "PA9_42") (pintype "bidirectional"))
    )
    (net (code "67") (name "USART2_RX") (class "Default")
      (node (ref "STM32F103RET6") (pin "17") (pinfunction "PA3_17") (pintype "bidirectional"))
      (node (ref "USART2") (pin "1") (pinfunction "1_1") (pintype "passive"))
    )
    (net (code "68") (name "USART2_TX") (class "Default")
      (node (ref "STM32F103RET6") (pin "16") (pinfunction "PA2_16") (pintype "bidirectional"))
      (node (ref "USART2") (pin "2") (pinfunction "2_2") (pintype "passive"))
    )
    (net (code "69") (name "USART3_CK") (class "Default")
      (node (ref "STM32F103RET6") (pin "53") (pinfunction "PC12_53") (pintype "bidirectional"))
    )
    (net (code "70") (name "USART3_RX") (class "Default")
      (node (ref "STM32F103RET6") (pin "52") (pinfunction "PC11_52") (pintype "bidirectional"))
    )
    (net (code "71") (name "USART3_TX") (class "Default")
      (node (ref "STM32F103RET6") (pin "51") (pinfunction "PC10_51") (pintype "bidirectional"))
    )
    (net (code "72") (name "V+") (class "Default")
      (node (ref "BAT60J") (pin "C") (pinfunction "C_C") (pintype "passive"))
      (node (ref "BAT60J_2") (pin "C") (pinfunction "C_C") (pintype "passive"))
      (node (ref "C3") (pin "+") (pinfunction "+_+") (pintype "passive"))
      (node (ref "R6") (pin "1") (pinfunction "1_1") (pintype "passive"))
      (node (ref "REG1117") (pin "3") (pinfunction "VIN_3") (pintype "input"))
      (node (ref "USART2") (pin "3") (pinfunction "3_3") (pintype "passive"))
    )
    (net (code "73") (name "VCC") (class "Default")
      (node (ref "C12") (pin "1") (pinfunction "1_1") (pintype "passive"))
      (node (ref "C14") (pin "1") (pinfunction "1_1") (pintype "passive"))
      (node (ref "C15") (pin "1") (pinfunction "1_1") (pintype "passive"))
      (node (ref "C17") (pin "1") (pinfunction "1_1") (pintype "passive"))
      (node (ref "C18") (pin "1") (pinfunction "1_1") (pintype "passive"))
      (node (ref "C4") (pin "2") (pinfunction "2_2") (pintype "passive"))
      (node (ref "C6") (pin "1") (pinfunction "1_1") (pintype "passive"))
      (node (ref "C7") (pin "+") (pinfunction "+_+") (pintype "passive"))
      (node (ref "EXP") (pin "7") (pinfunction "7_7") (pintype "passive"))
      (node (ref "FCM1608-0603") (pin "1") (pinfunction "P$1_1") (pintype "bidirectional"))
      (node (ref "I2C") (pin "3") (pinfunction "3_3") (pintype "passive"))
      (node (ref "NRF24L01+") (pin "2") (pinfunction "2_2") (pintype "passive"))
      (node (ref "R11") (pin "1") (pinfunction "1_1") (pintype "passive"))
      (node (ref "R18") (pin "1") (pinfunction "1_1") (pintype "passive"))
      (node (ref "R20") (pin "2") (pinfunction "2_2") (pintype "passive"))
      (node (ref "R7") (pin "1") (pinfunction "1_1") (pintype "passive"))
      (node (ref "R9") (pin "1") (pinfunction "1_1") (pintype "passive"))
      (node (ref "REG1117") (pin "2") (pinfunction "VOUT_2") (pintype "power_in"))
      (node (ref "REG1117") (pin "4") (pinfunction "VOUT_4") (pintype "power_in"))
      (node (ref "RFM22-S2") (pin "5") (pinfunction "VCC_5") (pintype "bidirectional"))
      (node (ref "STM32F103RET6") (pin "1") (pinfunction "VBAT_1") (pintype "power_in"))
      (node (ref "STM32F103RET6") (pin "19") (pinfunction "VDD_4_19") (pintype "power_in"))
      (node (ref "STM32F103RET6") (pin "32") (pinfunction "VDD_1_32") (pintype "power_in"))
      (node (ref "STM32F103RET6") (pin "48") (pinfunction "VDD_2_48") (pintype "power_in"))
      (node (ref "STM32F103RET6") (pin "64") (pinfunction "VDD_3_64") (pintype "power_in"))
      (node (ref "SWD") (pin "1") (pinfunction "1_1") (pintype "passive"))
    )
    (net (code "74") (name "unconnected-(RFM22-S2-GPIO2-Pad8)") (class "Default")
      (node (ref "RFM22-S2") (pin "8") (pinfunction "GPIO2_8") (pintype "bidirectional"))
    )
    (net (code "75") (name "unconnected-(STM32F103RET6B-PA11-Pad44)") (class "Default")
      (node (ref "STM32F103RET6") (pin "44") (pinfunction "PA11_44") (pintype "bidirectional"))
    )
    (net (code "76") (name "unconnected-(STM32F103RET6B-PA15-Pad50)") (class "Default")
      (node (ref "STM32F103RET6") (pin "50") (pinfunction "PA15_50") (pintype "bidirectional"))
    )
    (net (code "77") (name "unconnected-(STM32F103RET6C-PA0-Pad14)") (class "Default")
      (node (ref "STM32F103RET6") (pin "14") (pinfunction "PA0_14") (pintype "bidirectional"))
    )
    (net (code "78") (name "unconnected-(STM32F103RET6C-PA1-Pad15)") (class "Default")
      (node (ref "STM32F103RET6") (pin "15") (pinfunction "PA1_15") (pintype "bidirectional"))
    )
    (net (code "79") (name "unconnected-(STM32F103RET6C-PA4-Pad20)") (class "Default")
      (node (ref "STM32F103RET6") (pin "20") (pinfunction "PA4_20") (pintype "bidirectional"))
    )
    (net (code "80") (name "unconnected-(STM32F103RET6E-PB0-Pad26)") (class "Default")
      (node (ref "STM32F103RET6") (pin "26") (pinfunction "PB0_26") (pintype "bidirectional"))
    )
    (net (code "81") (name "unconnected-(STM32F103RET6E-PB1-Pad27)") (class "Default")
      (node (ref "STM32F103RET6") (pin "27") (pinfunction "PB1_27") (pintype "bidirectional"))
    )
    (net (code "82") (name "unconnected-(STM32F103RET6F-PC8-Pad39)") (class "Default")
      (node (ref "STM32F103RET6") (pin "39") (pinfunction "PC8_39") (pintype "bidirectional"))
    )
    (net (code "83") (name "unconnected-(STM32F103RET6F-PC13-Pad2)") (class "Default")
      (node (ref "STM32F103RET6") (pin "2") (pinfunction "PC13_2") (pintype "bidirectional"))
    )
    (net (code "84") (name "unconnected-(STM32F103RET6F-PC14-Pad3)") (class "Default")
      (node (ref "STM32F103RET6") (pin "3") (pinfunction "PC14_3") (pintype "bidirectional"))
    )
    (net (code "85") (name "unconnected-(STM32F103RET6F-PC15-Pad4)") (class "Default")
      (node (ref "STM32F103RET6") (pin "4") (pinfunction "PC15_4") (pintype "bidirectional"))
    )
    (net (code "86") (name "unconnected-(STM32F103RET6G-PC0-Pad8)") (class "Default")
      (node (ref "STM32F103RET6") (pin "8") (pinfunction "PC0_8") (pintype "bidirectional"))
    )
    (net (code "87") (name "unconnected-(STM32F103RET6G-PC3-Pad11)") (class "Default")
      (node (ref "STM32F103RET6") (pin "11") (pinfunction "PC3_11") (pintype "bidirectional"))
    )
    (net (code "88") (name "unconnected-(STM32F103RET6G-PC5-Pad25)") (class "Default")
      (node (ref "STM32F103RET6") (pin "25") (pinfunction "PC5_25") (pintype "bidirectional"))
    )
    (net (code "89") (name "unconnected-(STM32F103RET6H-PD2-Pad54)") (class "Default")
      (node (ref "STM32F103RET6") (pin "54") (pinfunction "PD2_54") (pintype "bidirectional"))
    )
  )
)
